# mcu.net
KiCad netlist of a schematic drawn in Altium Designer
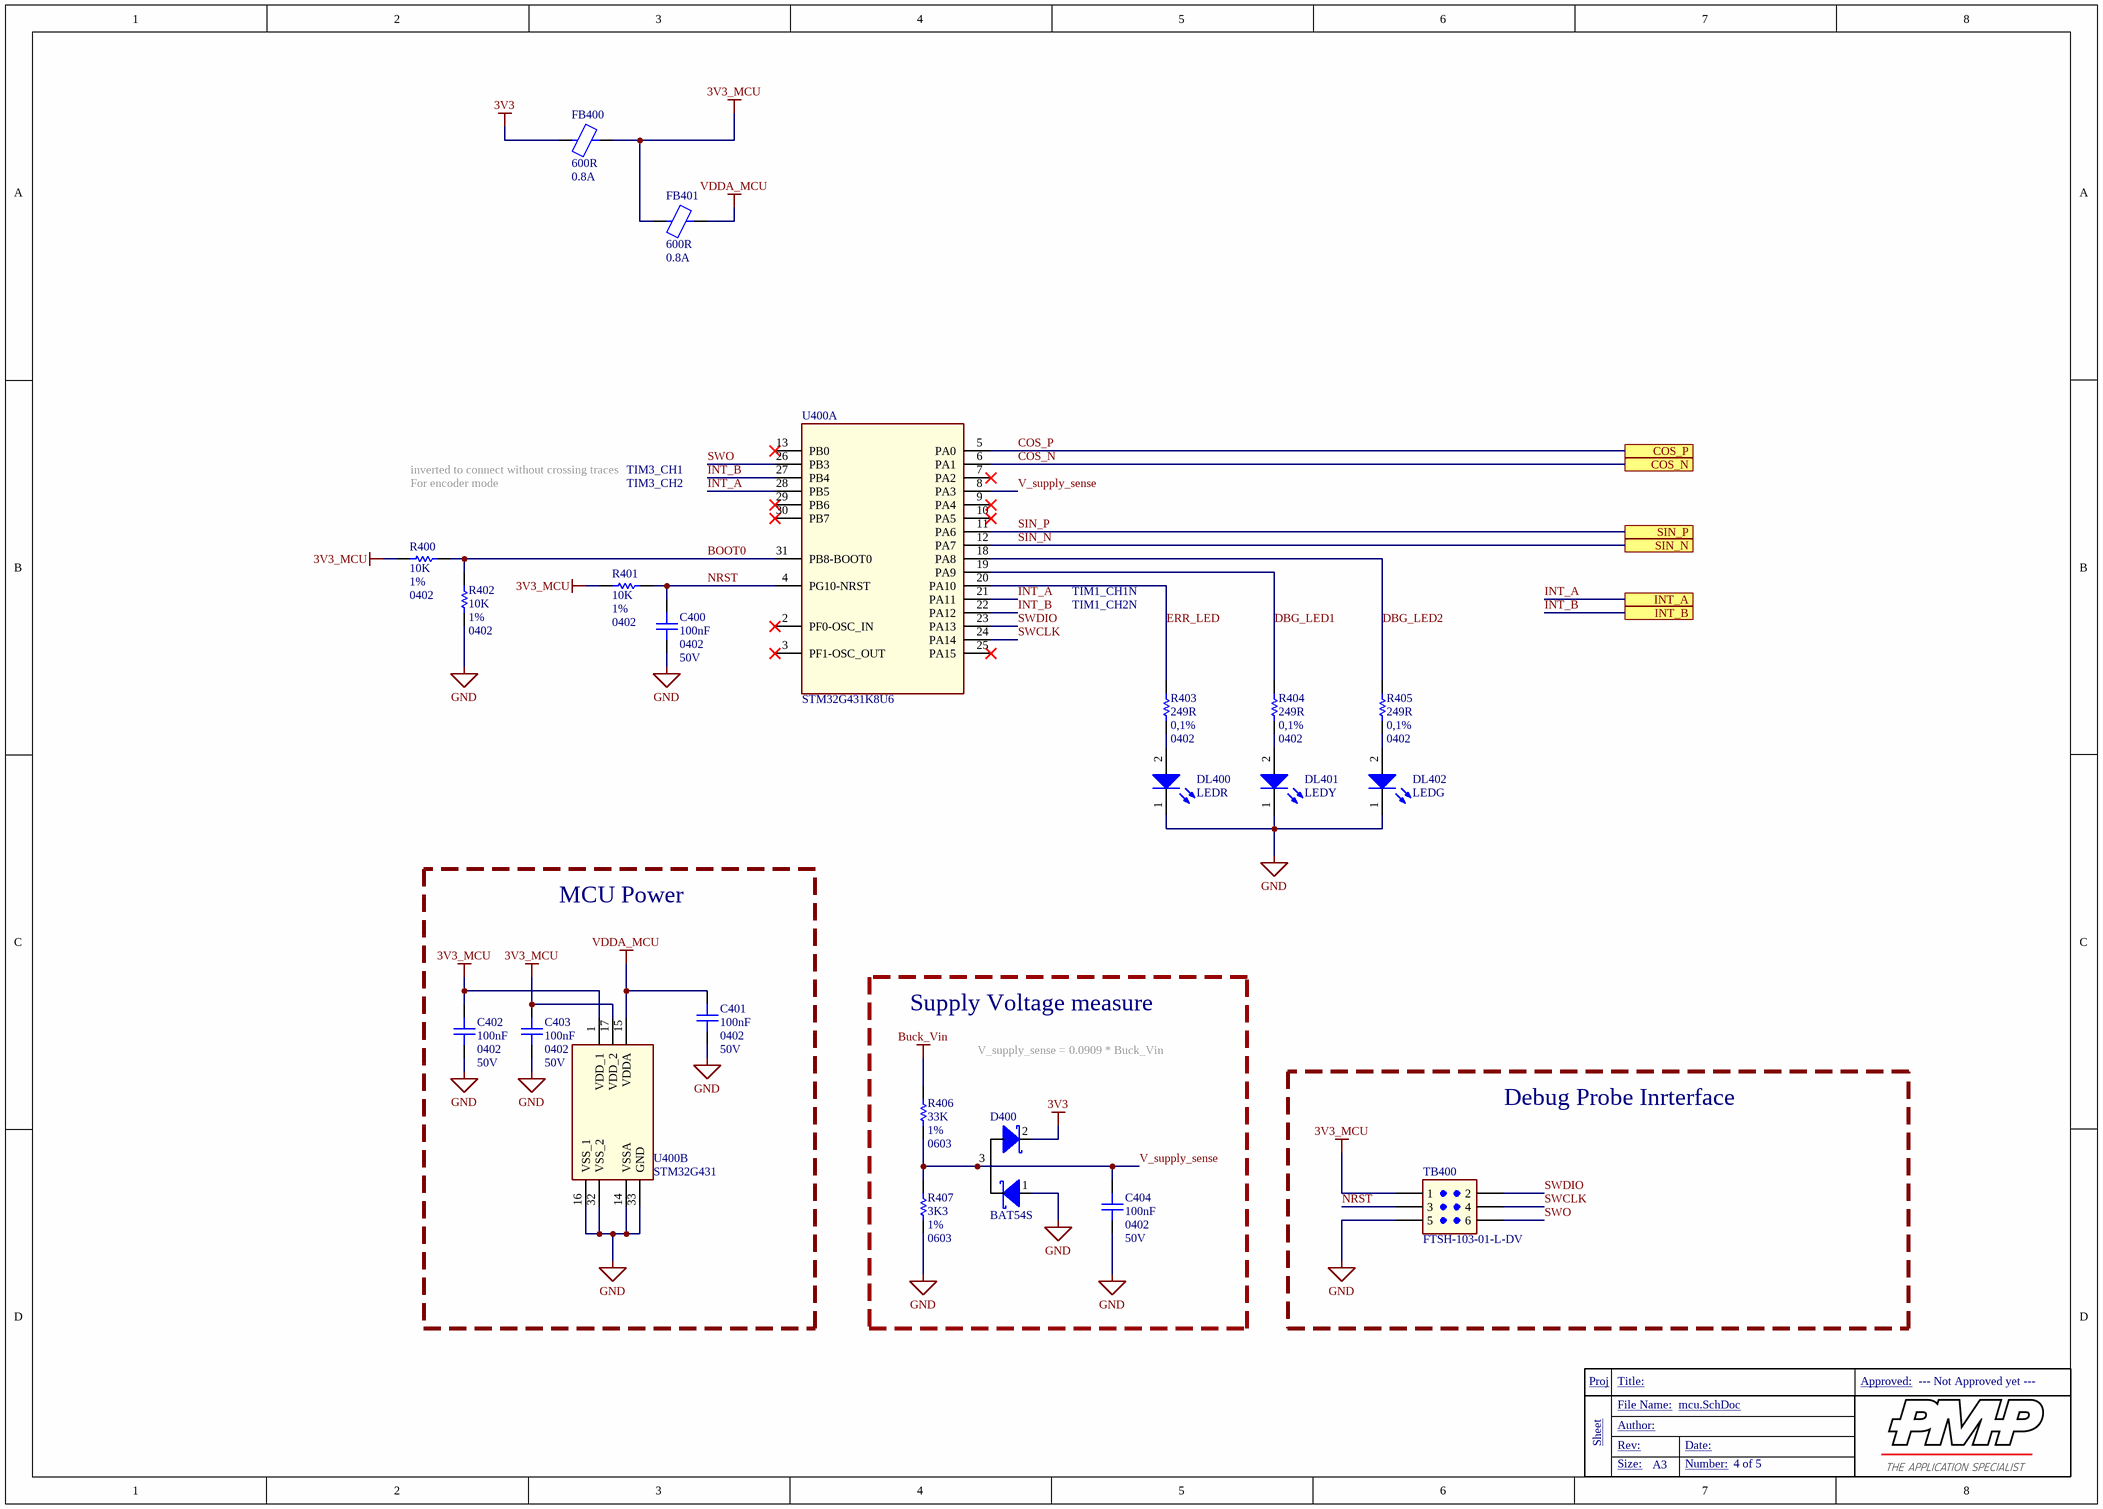
[diagram p0: mcu.SchDoc]

(export (version "E")
  (design (tool "Eeschema 10.0.6"))
  (components
    (comp (ref "C400")
      (value "100nF")
      (footprint "CER0402")
      (description "MLCC Automotive, 100nF, 0402, 50V, 10%, X7r")
      (fields
        (field (name "CASE/PACKAGE") "0402")
        (field (name "OP VOLTAGE") "50V")
        (field (name "TOLERANCE") "10%")
      )
      (libsource (lib "PMP_CapsDB") (part "CapCer_SMD_2"))
    )
    (comp (ref "C401")
      (value "100nF")
      (footprint "CER0402")
      (description "MLCC Automotive, 100nF, 0402, 50V, 10%, X7r")
      (fields
        (field (name "CASE/PACKAGE") "0402")
        (field (name "OP VOLTAGE") "50V")
        (field (name "TOLERANCE") "10%")
      )
      (libsource (lib "PMP_CapsDB") (part "CapCer_SMD_2"))
    )
    (comp (ref "C402")
      (value "100nF")
      (footprint "CER0402")
      (description "MLCC Automotive, 100nF, 0402, 50V, 10%, X7r")
      (fields
        (field (name "CASE/PACKAGE") "0402")
        (field (name "OP VOLTAGE") "50V")
        (field (name "TOLERANCE") "10%")
      )
      (libsource (lib "PMP_CapsDB") (part "CapCer_SMD_2"))
    )
    (comp (ref "C403")
      (value "100nF")
      (footprint "CER0402")
      (description "MLCC Automotive, 100nF, 0402, 50V, 10%, X7r")
      (fields
        (field (name "CASE/PACKAGE") "0402")
        (field (name "OP VOLTAGE") "50V")
        (field (name "TOLERANCE") "10%")
      )
      (libsource (lib "PMP_CapsDB") (part "CapCer_SMD_2"))
    )
    (comp (ref "C404")
      (value "100nF")
      (footprint "CER0402")
      (description "MLCC Automotive, 100nF, 0402, 50V, 10%, X7r")
      (fields
        (field (name "CASE/PACKAGE") "0402")
        (field (name "OP VOLTAGE") "50V")
        (field (name "TOLERANCE") "10%")
      )
      (libsource (lib "PMP_CapsDB") (part "CapCer_SMD_2"))
    )
    (comp (ref "D400")
      (value "BAT54S")
      (footprint "SOT95P230X110-3N")
      (description "Dual Schottky Diode,  Dual Series, SOT23, 0.2A, 30V")
      (fields (field (name "Comment") "Double Schottky Diode, SOT23-3 series"))
      (libsource (lib "Pmp_DiscretesDB") (part "SchottkyDual_SOT23_ AKC"))
    )
    (comp (ref "DL400")
      (value "LEDR")
      (footprint "LED SMD 0603")
      (description "LED standard - SMD Red 620nm 63mcd 2.2 V, 20mA, 0603 AECQ-102")
      (fields (field (name "Comment") "Single Color SMD LED"))
      (libsource (lib "Pmp_OptoDB") (part "LED_SMD_2_Single"))
    )
    (comp (ref "DL401")
      (value "LEDY")
      (footprint "LED_PLCC-4")
      (description "LED monocolore Yellow Power TOPLED")
      (fields (field (name "Comment") "Single Color SMD LED"))
      (libsource (lib "Pmp_OptoDB") (part "LED_SMD_2_Single"))
    )
    (comp (ref "DL402")
      (value "LEDG")
      (footprint "LED SMD 0603")
      (description "LED standard - SMD Grn 560nm 6.3mcd 2.2 V, 20mA, 0603 AECQ-102")
      (fields (field (name "Comment") "Single Color SMD LED"))
      (libsource (lib "Pmp_OptoDB") (part "LED_SMD_2_Single"))
    )
    (comp (ref "FB400")
      (value "~")
      (footprint "FEB0603")
      (description "SMD EMI Suppression Ferrite Bead 600R, 0603, For DC Power")
      (fields (field (name "IMPEDENCE @100MHZ") "600R") (field (name "RATED CURRENT @85°C") "0.8A"))
      (libsource (lib "PMP_FerriteDB") (part "FER_SMD_2_Ferrite_Bead"))
    )
    (comp (ref "FB401")
      (value "~")
      (footprint "FEB0603")
      (description "SMD EMI Suppression Ferrite Bead 600R, 0603, For DC Power")
      (fields (field (name "IMPEDENCE @100MHZ") "600R") (field (name "RATED CURRENT @85°C") "0.8A"))
      (libsource (lib "PMP_FerriteDB") (part "FER_SMD_2_Ferrite_Bead"))
    )
    (comp (ref "R400")
      (value "10K")
      (footprint "Res0402")
      (description "Thick Film SM Chip Resistors, 10K, 0402, ±1%, 1/10W")
      (fields
        (field (name "TOLERANCE") "1%")
        (field (name "CASE/PACKAGE") "0402")
        (field (name "POWER") "63mW")
        (field (name "Comment") "SMD Resistor")
      )
      (libsource (lib "PMP_ResDB") (part "Res_SMD_2"))
    )
    (comp (ref "R401")
      (value "10K")
      (footprint "Res0402")
      (description "Thick Film SM Chip Resistors, 10K, 0402, ±1%, 1/10W")
      (fields
        (field (name "TOLERANCE") "1%")
        (field (name "CASE/PACKAGE") "0402")
        (field (name "POWER") "63mW")
        (field (name "Comment") "SMD Resistor")
      )
      (libsource (lib "PMP_ResDB") (part "Res_SMD_2"))
    )
    (comp (ref "R402")
      (value "10K")
      (footprint "Res0402")
      (description "Thick Film SM Chip Resistors, 10K, 0402, ±1%, 1/10W")
      (fields
        (field (name "TOLERANCE") "1%")
        (field (name "CASE/PACKAGE") "0402")
        (field (name "POWER") "63mW")
        (field (name "Comment") "SMD Resistor")
      )
      (libsource (lib "PMP_ResDB") (part "Res_SMD_2"))
    )
    (comp (ref "R403")
      (value "249R")
      (footprint "Res0402")
      (description "Thick Film SM Chip Resistors, 249R, 0402, ±0.1%, 10ppm 1/16W")
      (fields
        (field (name "TOLERANCE") "0,1%")
        (field (name "CASE/PACKAGE") "0402")
        (field (name "POWER") "63mW")
        (field (name "Comment") "SMD Resistor")
      )
      (libsource (lib "PMP_ResDB") (part "Res_SMD_2"))
    )
    (comp (ref "R404")
      (value "249R")
      (footprint "Res0402")
      (description "Thick Film SM Chip Resistors, 249R, 0402, ±0.1%, 10ppm 1/16W")
      (fields
        (field (name "TOLERANCE") "0,1%")
        (field (name "CASE/PACKAGE") "0402")
        (field (name "POWER") "63mW")
        (field (name "Comment") "SMD Resistor")
      )
      (libsource (lib "PMP_ResDB") (part "Res_SMD_2"))
    )
    (comp (ref "R405")
      (value "249R")
      (footprint "Res0402")
      (description "Thick Film SM Chip Resistors, 249R, 0402, ±0.1%, 10ppm 1/16W")
      (fields
        (field (name "TOLERANCE") "0,1%")
        (field (name "CASE/PACKAGE") "0402")
        (field (name "POWER") "63mW")
        (field (name "Comment") "SMD Resistor")
      )
      (libsource (lib "PMP_ResDB") (part "Res_SMD_2"))
    )
    (comp (ref "R406")
      (value "33K")
      (footprint "Res0603")
      (description "Thick Film SM Chip Resistors, 33K, 0603, ±1%, 1/10W")
      (fields
        (field (name "TOLERANCE") "1%")
        (field (name "CASE/PACKAGE") "0603")
        (field (name "POWER") "100mW")
        (field (name "Comment") "SMD Resistor")
      )
      (libsource (lib "PMP_ResDB") (part "Res_SMD_2"))
    )
    (comp (ref "R407")
      (value "3K3")
      (footprint "Res0603")
      (description "Thick Film SM Chip Resistors, 3K3, 0603, ±1%, 1/10W")
      (fields
        (field (name "TOLERANCE") "1%")
        (field (name "CASE/PACKAGE") "0603")
        (field (name "POWER") "100mW")
        (field (name "Comment") "SMD Resistor")
      )
      (libsource (lib "PMP_ResDB") (part "Res_SMD_2"))
    )
    (comp (ref "TB400")
      (value "FTSH-103-01-L-DV")
      (footprint "SAMTEC_FTSH-103_3x2_SMD")
      (description "Samtech FTSH Header, 6pin (3x2), pitch 1.27mm, for Arm Jtag")
      (fields (field (name "Comment") "TC2030_NL"))
      (libsource (lib "PMP_ConnectorsDB") (part "TC2030_NL"))
    )
    (comp (ref "U400")
      (value "STM32G431K8U6")
      (footprint "QFN50P500X500X60-NOPAD")
      (description "MCU  Arm Cortex-M4 MCU 170 MHz -64 KB Flash")
      (fields
        (field (name "MOUSER PART NUMBER") "511-STM32G431K8U6")
        (field (name "MANUFACTURER_PART_NUMBER") "STM32G431K8U6")
      )
      (libsource (lib "PMP_ICsDB") (part "STM32G431K8U6"))
    )
  )
  (nets
    (net (code "1") (name "/BOOT0") (class "Default")
      (node (ref "R400") (pin "1") (pinfunction "1_1") (pintype "passive"))
      (node (ref "R402") (pin "2") (pinfunction "2_2") (pintype "passive"))
      (node (ref "U400") (pin "31") (pinfunction "PB8-BOOT0_31") (pintype "passive"))
    )
    (net (code "2") (name "/COS_N") (class "Default")
      (node (ref "U400") (pin "6") (pinfunction "PA1_6") (pintype "passive"))
    )
    (net (code "3") (name "/COS_P") (class "Default")
      (node (ref "U400") (pin "5") (pinfunction "PA0_5") (pintype "passive"))
    )
    (net (code "4") (name "/DBG_LED1") (class "Default")
      (node (ref "R404") (pin "2") (pinfunction "2_2") (pintype "passive"))
      (node (ref "U400") (pin "19") (pinfunction "PA9_19") (pintype "passive"))
    )
    (net (code "5") (name "/DBG_LED2") (class "Default")
      (node (ref "R405") (pin "2") (pinfunction "2_2") (pintype "passive"))
      (node (ref "U400") (pin "18") (pinfunction "PA8_18") (pintype "passive"))
    )
    (net (code "6") (name "/ERR_LED") (class "Default")
      (node (ref "R403") (pin "2") (pinfunction "2_2") (pintype "passive"))
      (node (ref "U400") (pin "20") (pinfunction "PA10_20") (pintype "passive"))
    )
    (net (code "7") (name "/INT_A") (class "Default")
      (node (ref "U400") (pin "21") (pinfunction "PA11_21") (pintype "passive"))
      (node (ref "U400") (pin "28") (pinfunction "PB5_28") (pintype "passive"))
    )
    (net (code "8") (name "/INT_B") (class "Default")
      (node (ref "U400") (pin "22") (pinfunction "PA12_22") (pintype "passive"))
      (node (ref "U400") (pin "27") (pinfunction "PB4_27") (pintype "passive"))
    )
    (net (code "9") (name "/NRST") (class "Default")
      (node (ref "C400") (pin "1") (pinfunction "1_1") (pintype "passive"))
      (node (ref "R401") (pin "1") (pinfunction "1_1") (pintype "passive"))
      (node (ref "TB400") (pin "3") (pinfunction "3_3") (pintype "passive"))
      (node (ref "U400") (pin "4") (pinfunction "PG10-NRST_4") (pintype "passive"))
    )
    (net (code "10") (name "/SIN_N") (class "Default")
      (node (ref "U400") (pin "12") (pinfunction "PA7_12") (pintype "passive"))
    )
    (net (code "11") (name "/SIN_P") (class "Default")
      (node (ref "U400") (pin "11") (pinfunction "PA6_11") (pintype "passive"))
    )
    (net (code "12") (name "/SWCLK") (class "Default")
      (node (ref "TB400") (pin "4") (pinfunction "4_4") (pintype "passive"))
      (node (ref "U400") (pin "24") (pinfunction "PA14_24") (pintype "passive"))
    )
    (net (code "13") (name "/SWDIO") (class "Default")
      (node (ref "TB400") (pin "2") (pinfunction "2_2") (pintype "passive"))
      (node (ref "U400") (pin "23") (pinfunction "PA13_23") (pintype "passive"))
    )
    (net (code "14") (name "/SWO") (class "Default")
      (node (ref "TB400") (pin "6") (pinfunction "6_6") (pintype "passive"))
      (node (ref "U400") (pin "26") (pinfunction "PB3_26") (pintype "passive"))
    )
    (net (code "15") (name "/V_supply_sense") (class "Default")
      (node (ref "C404") (pin "1") (pinfunction "1_1") (pintype "passive"))
      (node (ref "D400") (pin "3") (pinfunction "C_3") (pintype "passive"))
      (node (ref "R406") (pin "1") (pinfunction "1_1") (pintype "passive"))
      (node (ref "R407") (pin "2") (pinfunction "2_2") (pintype "passive"))
      (node (ref "U400") (pin "8") (pinfunction "PA3_8") (pintype "passive"))
    )
    (net (code "16") (name "3V3") (class "Default")
      (node (ref "D400") (pin "2") (pinfunction "K2_2") (pintype "passive"))
      (node (ref "FB400") (pin "1") (pinfunction "1_1") (pintype "passive"))
    )
    (net (code "17") (name "3V3_MCU") (class "Default")
      (node (ref "C402") (pin "1") (pinfunction "1_1") (pintype "passive"))
      (node (ref "C403") (pin "1") (pinfunction "1_1") (pintype "passive"))
      (node (ref "FB400") (pin "2") (pinfunction "2_2") (pintype "passive"))
      (node (ref "FB401") (pin "1") (pinfunction "1_1") (pintype "passive"))
      (node (ref "R400") (pin "2") (pinfunction "2_2") (pintype "passive"))
      (node (ref "R401") (pin "2") (pinfunction "2_2") (pintype "passive"))
      (node (ref "TB400") (pin "1") (pinfunction "1_1") (pintype "passive"))
      (node (ref "U400") (pin "1") (pinfunction "VDD_1_1") (pintype "passive"))
      (node (ref "U400") (pin "17") (pinfunction "VDD_2_17") (pintype "passive"))
    )
    (net (code "18") (name "Buck_Vin") (class "Default")
      (node (ref "R406") (pin "2") (pinfunction "2_2") (pintype "passive"))
    )
    (net (code "19") (name "GND") (class "Default")
      (node (ref "C400") (pin "2") (pinfunction "2_2") (pintype "passive"))
      (node (ref "C401") (pin "2") (pinfunction "2_2") (pintype "passive"))
      (node (ref "C402") (pin "2") (pinfunction "2_2") (pintype "passive"))
      (node (ref "C403") (pin "2") (pinfunction "2_2") (pintype "passive"))
      (node (ref "C404") (pin "2") (pinfunction "2_2") (pintype "passive"))
      (node (ref "D400") (pin "1") (pinfunction "A1_1") (pintype "passive"))
      (node (ref "DL400") (pin "1") (pinfunction "K_1") (pintype "passive"))
      (node (ref "DL401") (pin "1") (pinfunction "K_1") (pintype "passive"))
      (node (ref "DL402") (pin "1") (pinfunction "K_1") (pintype "passive"))
      (node (ref "R402") (pin "1") (pinfunction "1_1") (pintype "passive"))
      (node (ref "R407") (pin "1") (pinfunction "1_1") (pintype "passive"))
      (node (ref "TB400") (pin "5") (pinfunction "5_5") (pintype "passive"))
      (node (ref "U400") (pin "14") (pinfunction "VSSA_14") (pintype "passive"))
      (node (ref "U400") (pin "16") (pinfunction "VSS_1_16") (pintype "passive"))
      (node (ref "U400") (pin "32") (pinfunction "VSS_2_32") (pintype "passive"))
      (node (ref "U400") (pin "33") (pinfunction "GND_33") (pintype "passive"))
    )
    (net (code "20") (name "Net-(DL400-A)") (class "Default")
      (node (ref "DL400") (pin "2") (pinfunction "A_2") (pintype "passive"))
      (node (ref "R403") (pin "1") (pinfunction "1_1") (pintype "passive"))
    )
    (net (code "21") (name "Net-(DL401-A)") (class "Default")
      (node (ref "DL401") (pin "2") (pinfunction "A_2") (pintype "passive"))
      (node (ref "R404") (pin "1") (pinfunction "1_1") (pintype "passive"))
    )
    (net (code "22") (name "Net-(DL402-A)") (class "Default")
      (node (ref "DL402") (pin "2") (pinfunction "A_2") (pintype "passive"))
      (node (ref "R405") (pin "1") (pinfunction "1_1") (pintype "passive"))
    )
    (net (code "23") (name "VDDA_MCU") (class "Default")
      (node (ref "C401") (pin "1") (pinfunction "1_1") (pintype "passive"))
      (node (ref "FB401") (pin "2") (pinfunction "2_2") (pintype "passive"))
      (node (ref "U400") (pin "15") (pinfunction "VDDA_15") (pintype "passive"))
    )
    (net (code "24") (name "unconnected-(U400A-PA2-Pad7)") (class "Default")
      (node (ref "U400") (pin "7") (pinfunction "PA2_7") (pintype "passive+no_connect"))
    )
    (net (code "25") (name "unconnected-(U400A-PA4-Pad9)") (class "Default")
      (node (ref "U400") (pin "9") (pinfunction "PA4_9") (pintype "passive+no_connect"))
    )
    (net (code "26") (name "unconnected-(U400A-PA5-Pad10)") (class "Default")
      (node (ref "U400") (pin "10") (pinfunction "PA5_10") (pintype "passive+no_connect"))
    )
    (net (code "27") (name "unconnected-(U400A-PA15-Pad25)") (class "Default")
      (node (ref "U400") (pin "25") (pinfunction "PA15_25") (pintype "passive+no_connect"))
    )
    (net (code "28") (name "unconnected-(U400A-PB0-Pad13)") (class "Default")
      (node (ref "U400") (pin "13") (pinfunction "PB0_13") (pintype "passive+no_connect"))
    )
    (net (code "29") (name "unconnected-(U400A-PB6-Pad29)") (class "Default")
      (node (ref "U400") (pin "29") (pinfunction "PB6_29") (pintype "passive+no_connect"))
    )
    (net (code "30") (name "unconnected-(U400A-PB7-Pad30)") (class "Default")
      (node (ref "U400") (pin "30") (pinfunction "PB7_30") (pintype "passive+no_connect"))
    )
    (net (code "31") (name "unconnected-(U400A-PF0-OSC_IN-Pad2)") (class "Default")
      (node (ref "U400") (pin "2") (pinfunction "PF0-OSC_IN_2") (pintype "passive+no_connect"))
    )
    (net (code "32") (name "unconnected-(U400A-PF1-OSC_OUT-Pad3)") (class "Default")
      (node (ref "U400") (pin "3") (pinfunction "PF1-OSC_OUT_3") (pintype "passive+no_connect"))
    )
  )
)
